# Power.net
KiCad netlist of a schematic drawn in Altium Designer
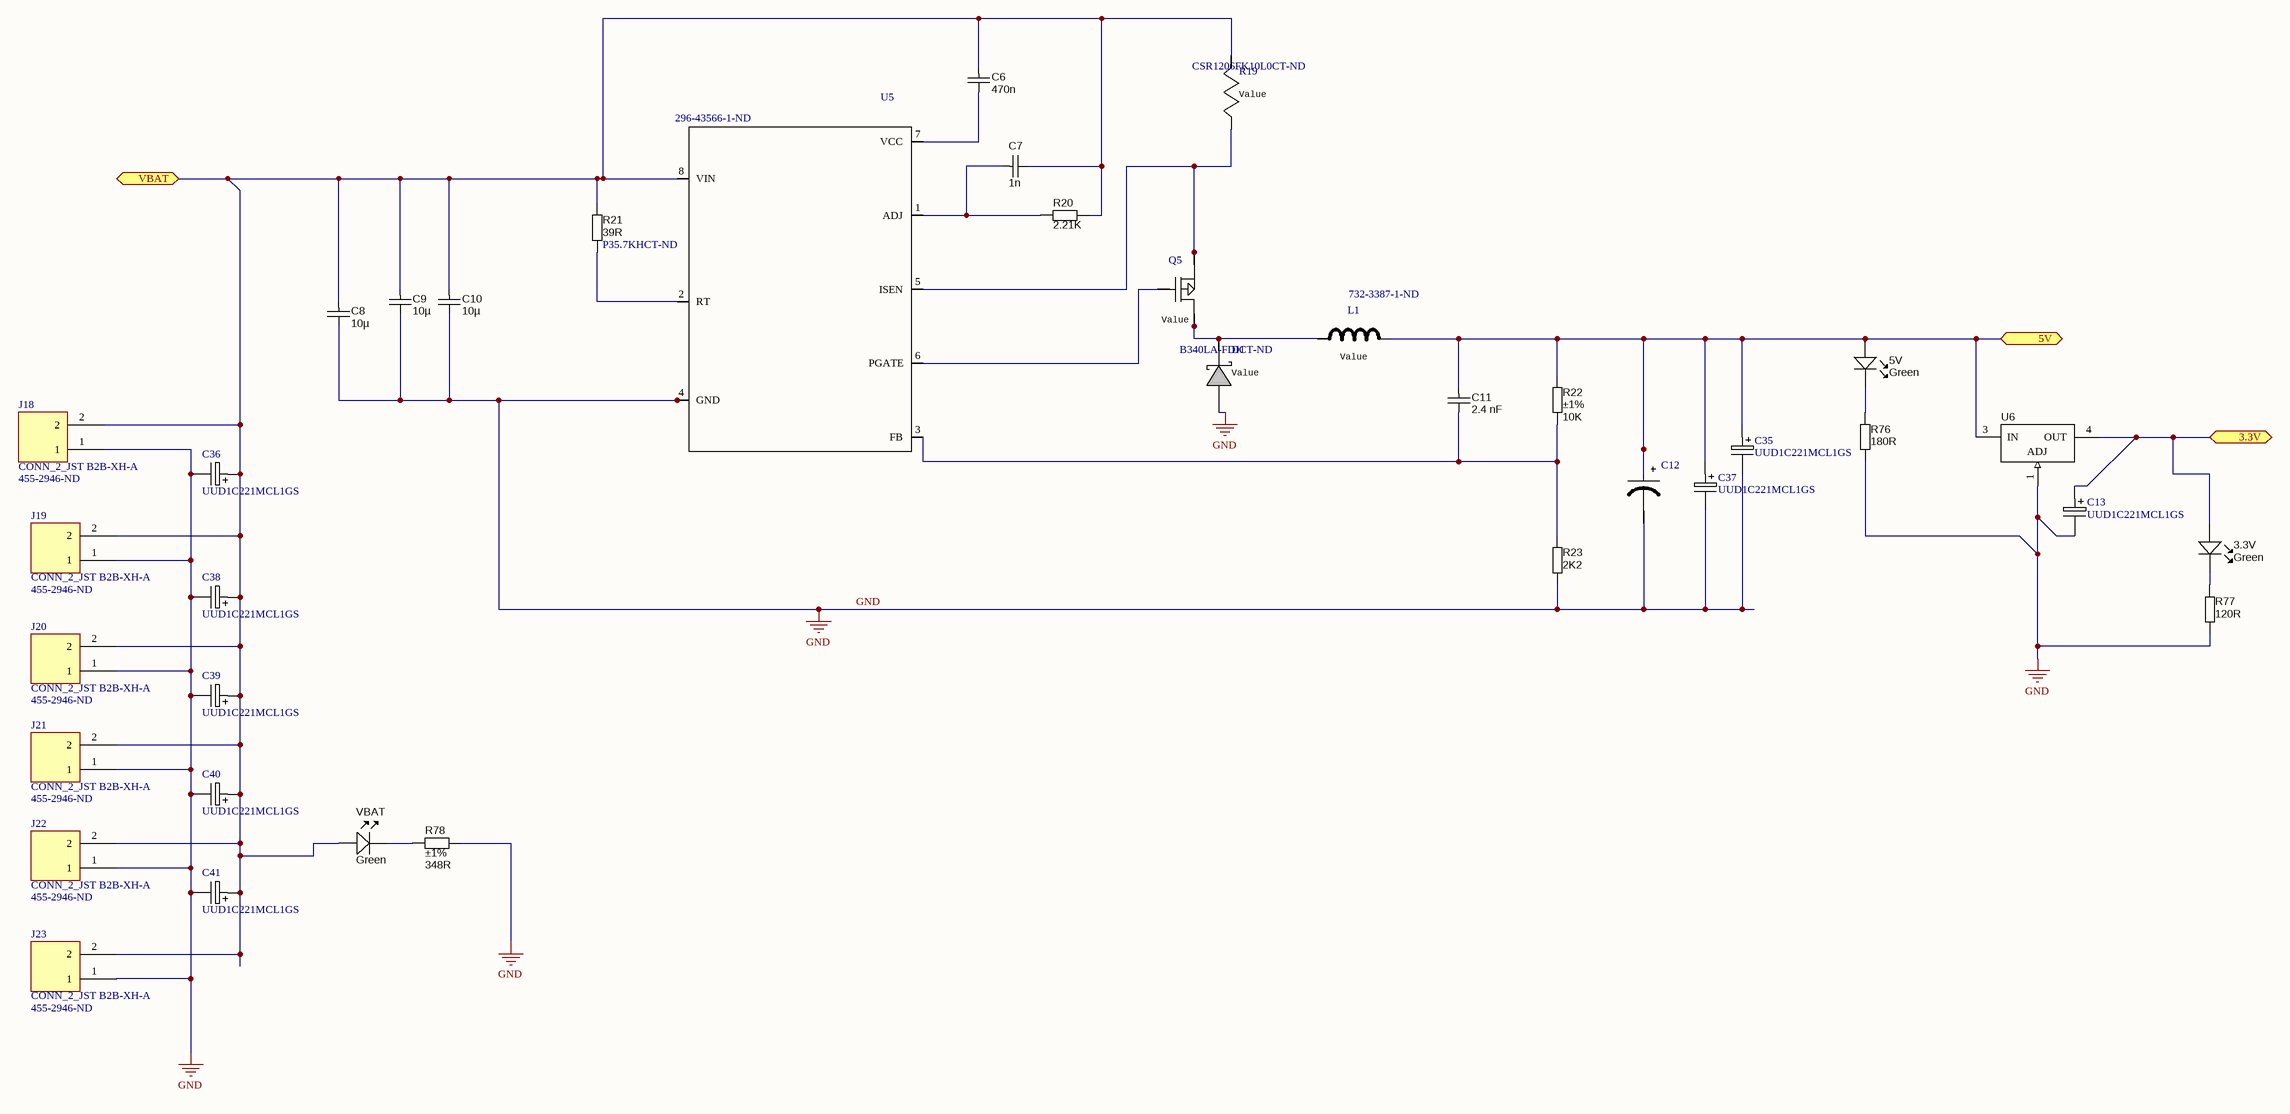
[diagram p0: Power.schdoc]

(export (version "E")
  (design (tool "Eeschema 10.0.6"))
  (components
    (comp (ref "3.3V")
      (value "Green")
      (footprint "LED-0603-GREEN")
      (description "LED 0603 SMD Green 525nm 350mcd 20mA")
      (libsource (lib "PBL - Light Sources") (part "LED_SMD_Green_0603_525nm_350mcd"))
    )
    (comp (ref "5V")
      (value "Green")
      (footprint "LED-0603-GREEN")
      (description "LED 0603 SMD Green 525nm 350mcd 20mA")
      (libsource (lib "PBL - Light Sources") (part "LED_SMD_Green_0603_525nm_350mcd"))
    )
    (comp (ref "C6")
      (value "470n")
      (footprint "CAPC2012X135N")
      (description "Capacitor SMD Cer 470nF 10% 16V X7R 0805")
      (fields (field (name "TOLERANCE") "±10%") (field (name "Comment") "approved sub OK"))
      (libsource (lib "PBL - Capacitors") (part "CAPC_470n_0805_X7R_16V_10%"))
    )
    (comp (ref "C7")
      (value "1n")
      (footprint "CAPC1608X90N")
      (description "Capacitor SMD Cer 1nF 10% 100V X7R 0603")
      (fields (field (name "TOLERANCE") "±10%") (field (name "Comment") "approved sub OK"))
      (libsource (lib "PBL - Capacitors") (part "CAPC_1n_0603_X7R_100V_10%"))
    )
    (comp (ref "C8")
      (value "10µ")
      (footprint "CAPC3216X180N")
      (description "Capacitor SMD Cer 10uF 10% 16V X7R 1206")
      (fields (field (name "TOLERANCE") "±10%") (field (name "Comment") "approved sub OK"))
      (libsource (lib "PBL - Capacitors") (part "CAPC_10u_1206_16V"))
    )
    (comp (ref "C9")
      (value "10µ")
      (footprint "CAPC3216X180N")
      (description "Capacitor SMD Cer 10uF 10% 16V X7R 1206")
      (fields (field (name "TOLERANCE") "±10%") (field (name "Comment") "approved sub OK"))
      (libsource (lib "PBL - Capacitors") (part "CAPC_10u_1206_16V"))
    )
    (comp (ref "C10")
      (value "10µ")
      (footprint "CAPC3216X180N")
      (description "Capacitor SMD Cer 10uF 10% 16V X7R 1206")
      (fields (field (name "TOLERANCE") "±10%") (field (name "Comment") "approved sub OK"))
      (libsource (lib "PBL - Capacitors") (part "CAPC_10u_1206_16V"))
    )
    (comp (ref "C11")
      (value "2.4 nF")
      (footprint "CAPC1608X90N")
      (description "Capacitor SMD Cer 2400pF  50V NP0 0603")
      (fields (field (name "TOLERANCE") "±0.25pF") (field (name "Comment") "approved sub OK"))
      (libsource (lib "PBL - Capacitors") (part "CAPC_2n4_50V_0603"))
    )
    (comp (ref "C12")
      (value "6TPU47MSI")
      (footprint "CAPC2012X135N")
      (description "CAP TANT POLY 47UF 6.3V 0805")
      (libsource (lib "PBL - Capacitors") (part "CAPT_47u_6.3V_0805_6TPU47MSI"))
    )
    (comp (ref "C13")
      (value "UUD1C221MCL1GS")
      (footprint "NICH 6.3mm 7.7mm")
      (description "GENERIC CAPACITOR POLARISED")
      (libsource (lib "SMD Capacitors Electrolytic") (part "NICHICON_220uF_16V"))
    )
    (comp (ref "C35")
      (value "UUD1C221MCL1GS")
      (footprint "NICH 6.3mm 7.7mm")
      (description "GENERIC CAPACITOR POLARISED")
      (libsource (lib "SMD Capacitors Electrolytic") (part "NICHICON_220uF_16V"))
    )
    (comp (ref "C36")
      (value "UUD1C221MCL1GS")
      (footprint "NICH 6.3mm 7.7mm")
      (description "GENERIC CAPACITOR POLARISED")
      (libsource (lib "SMD Capacitors Electrolytic") (part "NICHICON_220uF_16V"))
    )
    (comp (ref "C37")
      (value "UUD1C221MCL1GS")
      (footprint "NICH 6.3mm 7.7mm")
      (description "GENERIC CAPACITOR POLARISED")
      (libsource (lib "SMD Capacitors Electrolytic") (part "NICHICON_220uF_16V"))
    )
    (comp (ref "C38")
      (value "UUD1C221MCL1GS")
      (footprint "NICH 6.3mm 7.7mm")
      (description "GENERIC CAPACITOR POLARISED")
      (libsource (lib "SMD Capacitors Electrolytic") (part "NICHICON_220uF_16V"))
    )
    (comp (ref "C39")
      (value "UUD1C221MCL1GS")
      (footprint "NICH 6.3mm 7.7mm")
      (description "GENERIC CAPACITOR POLARISED")
      (libsource (lib "SMD Capacitors Electrolytic") (part "NICHICON_220uF_16V"))
    )
    (comp (ref "C40")
      (value "UUD1C221MCL1GS")
      (footprint "NICH 6.3mm 7.7mm")
      (description "GENERIC CAPACITOR POLARISED")
      (libsource (lib "SMD Capacitors Electrolytic") (part "NICHICON_220uF_16V"))
    )
    (comp (ref "C41")
      (value "UUD1C221MCL1GS")
      (footprint "NICH 6.3mm 7.7mm")
      (description "GENERIC CAPACITOR POLARISED")
      (libsource (lib "SMD Capacitors Electrolytic") (part "NICHICON_220uF_16V"))
    )
    (comp (ref "D1")
      (value "Value")
      (footprint "SMA")
      (description "Imported")
      (fields
        (field (name "MANUFACTURER_PART_NUMBER") "B340LA-13-F")
        (field (name "SUPPLIER PART NUMBER 1") "B340LA-FDICT-ND")
      )
      (libsource (lib "2016-02-21_13-02-55") (part "B340LA-13-F"))
    )
    (comp (ref "J18")
      (value "CONN_2_JST B2B-XH-A")
      (footprint "CONN_JST_XT_TH_2")
      (description "CONN HEADER XH SIDE 2POS 2.5MM")
      (fields (field (name "SUPPLIER PART NUMBER 1") "455-2946-ND"))
      (libsource (lib "RyanMasterLib") (part "CONN_2_JST B2B-XH-A"))
    )
    (comp (ref "J19")
      (value "CONN_2_JST B2B-XH-A")
      (footprint "CONN_JST_XT_TH_2")
      (description "CONN HEADER XH SIDE 2POS 2.5MM")
      (fields (field (name "SUPPLIER PART NUMBER 1") "455-2946-ND"))
      (libsource (lib "RyanMasterLib") (part "CONN_2_JST B2B-XH-A"))
    )
    (comp (ref "J20")
      (value "CONN_2_JST B2B-XH-A")
      (footprint "CONN_JST_XT_TH_2")
      (description "CONN HEADER XH SIDE 2POS 2.5MM")
      (fields (field (name "SUPPLIER PART NUMBER 1") "455-2946-ND"))
      (libsource (lib "RyanMasterLib") (part "CONN_2_JST B2B-XH-A"))
    )
    (comp (ref "J21")
      (value "CONN_2_JST B2B-XH-A")
      (footprint "CONN_JST_XT_TH_2")
      (description "CONN HEADER XH SIDE 2POS 2.5MM")
      (fields (field (name "SUPPLIER PART NUMBER 1") "455-2946-ND"))
      (libsource (lib "RyanMasterLib") (part "CONN_2_JST B2B-XH-A"))
    )
    (comp (ref "J22")
      (value "CONN_2_JST B2B-XH-A")
      (footprint "CONN_JST_XT_TH_2")
      (description "CONN HEADER XH SIDE 2POS 2.5MM")
      (fields (field (name "SUPPLIER PART NUMBER 1") "455-2946-ND"))
      (libsource (lib "RyanMasterLib") (part "CONN_2_JST B2B-XH-A"))
    )
    (comp (ref "J23")
      (value "CONN_2_JST B2B-XH-A")
      (footprint "CONN_JST_XT_TH_2")
      (description "CONN HEADER XH SIDE 2POS 2.5MM")
      (fields (field (name "SUPPLIER PART NUMBER 1") "455-2946-ND"))
      (libsource (lib "RyanMasterLib") (part "CONN_2_JST B2B-XH-A"))
    )
    (comp (ref "L1")
      (value "Value")
      (footprint "IND_WE-LHMI-SM")
      (description "Imported")
      (fields
        (field (name "MANUFACTURER_PART_NUMBER") "74437368022")
        (field (name "MANUFACTURER") "Wurth Elektronik")
        (field (name "SUPPLIER PART NUMBER 1") "732-3387-1-ND")
      )
      (libsource (lib "2016-02-21_13-02-55") (part "74437368022"))
    )
    (comp (ref "Q5")
      (value "Value")
      (footprint "TRANS_NEXFET_Q3A")
      (description "Imported")
      (fields (field (name "PARTNUMBER") "CSD25402Q3A") (field (name "MANUFACTURER") "Texas Instruments"))
      (libsource (lib "2016-02-21_13-02-55") (part "CSD25402Q3A"))
    )
    (comp (ref "R19")
      (value "Value")
      (footprint "1206")
      (description "Imported")
      (fields
        (field (name "MANUFACTURER_PART_NUMBER") "CSR1206FK10L0")
        (field (name "SUPPLIER PART NUMBER 1") "CSR1206FK10L0CT-ND")
      )
      (libsource (lib "2016-02-21_13-02-55") (part "CSR1206FK10L0"))
    )
    (comp (ref "R20")
      (value "2.21K")
      (footprint "RESC1608X55N")
      (description "Resistor SMD chip 2.21k Ohm 0.1W 1% 0603")
      (fields (field (name "TOLERANCE") "±5%") (field (name "Comment") "Thick Film"))
      (libsource (lib "PBL - Resistors") (part "RES_2.21K_0603_1%"))
    )
    (comp (ref "R21")
      (value "39R")
      (footprint "RESC1608X55N")
      (description "Resistor SMD chip 35.7K Ohm 0.1W 1% 0603")
      (fields
        (field (name "TOLERANCE") "±5%")
        (field (name "SUPPLIER PART NUMBER 1") "P35.7KHCT-ND")
        (field (name "Comment") "Thick Film")
      )
      (libsource (lib "PBL - Resistors") (part "RES_35.7K_0603_1%"))
    )
    (comp (ref "R22")
      (value "10K")
      (footprint "RESC1608X55N")
      (description "Resistor SMD chip 10k Ohm 0.1W 1% 0603")
      (fields (field (name "TOLERANCE") "±1%") (field (name "Comment") "Thick Film"))
      (libsource (lib "PBL - Resistors") (part "RES_10K_0603_1%"))
    )
    (comp (ref "R23")
      (value "2K2")
      (footprint "RESC1608X55N")
      (description "Resistor SMD chip 2.2k Ohm 0.1W 1% 0603")
      (fields (field (name "TOLERANCE") "±5%") (field (name "Comment") "Thick Film"))
      (libsource (lib "PBL - Resistors") (part "RES_2K2_0603_1%"))
    )
    (comp (ref "R76")
      (value "180R")
      (footprint "RESC1608X55N")
      (description "Resistor SMD chip 180 Ohm 0.1W 5% 0603")
      (fields (field (name "TOLERANCE") "±5%") (field (name "Comment") "Thick Film"))
      (libsource (lib "PBL - Resistors") (part "RES_180R_0603_5%"))
    )
    (comp (ref "R77")
      (value "120R")
      (footprint "RESC1608X55N")
      (description "Resistor SMD chip 120 Ohm 0.1W 5% 0603")
      (fields (field (name "TOLERANCE") "±5%") (field (name "Comment") "Thick Film"))
      (libsource (lib "PBL - Resistors") (part "RES_120R_0603_5%"))
    )
    (comp (ref "R78")
      (value "348R")
      (footprint "RESC1608X55N")
      (description "Resistor SMD chip 348 Ohm 0.1W 1% 0603")
      (fields (field (name "TOLERANCE") "±1%") (field (name "Comment") "Thin Film"))
      (libsource (lib "PBL - Resistors") (part "RES_348R_0603_1%"))
    )
    (comp (ref "U5")
      (value "LM25085AMY/NOPB")
      (footprint "MUY08A")
      (description "Imported")
      (fields
        (field (name "MANUFACTURER_PART_NUMBER") "LM5085MY/NOPB")
        (field (name "SUPPLIER PART NUMBER 1") "296-43566-1-ND")
      )
      (libsource (lib "2016-02-21_13-02-55") (part "LM25085AMY/NOPB"))
    )
    (comp (ref "U6")
      (value "LD1085D2T33R")
      (footprint "D2PAK-3")
      (description "Voltage Regulator IC, IC REG LDO 3.3V 3A D2PAK")
      (fields (field (name "TOLERANCE") "0.04%"))
      (libsource (lib "PBL - Regulators") (part "LD1085D2T33R"))
    )
    (comp (ref "VBAT")
      (value "Green")
      (footprint "LED-0603-GREEN")
      (description "LED 0603 SMD Green 525nm 350mcd 20mA")
      (libsource (lib "PBL - Light Sources") (part "LED_SMD_Green_0603_525nm_350mcd"))
    )
  )
  (nets
    (net (code "1") (name "/3.3V") (class "Default")
      (node (ref "3.3V") (pin "A") (pinfunction "A_A") (pintype "passive"))
      (node (ref "C13") (pin "+") (pinfunction "+_+") (pintype "passive"))
      (node (ref "U6") (pin "4") (pinfunction "OUT_4") (pintype "power_in"))
    )
    (net (code "2") (name "/5V") (class "Default")
      (node (ref "5V") (pin "A") (pinfunction "A_A") (pintype "passive"))
      (node (ref "C11") (pin "1") (pintype "passive"))
      (node (ref "C12") (pin "1") (pinfunction "+_1") (pintype "passive"))
      (node (ref "C35") (pin "+") (pinfunction "+_+") (pintype "passive"))
      (node (ref "C37") (pin "+") (pinfunction "+_+") (pintype "passive"))
      (node (ref "L1") (pin "2") (pinfunction "2_2") (pintype "passive"))
      (node (ref "R22") (pin "1") (pinfunction "1_1") (pintype "passive"))
      (node (ref "U6") (pin "3") (pinfunction "IN_3") (pintype "power_in"))
    )
    (net (code "3") (name "/VBAT") (class "Default")
      (node (ref "C10") (pin "1") (pintype "passive"))
      (node (ref "C36") (pin "+") (pinfunction "+_+") (pintype "passive"))
      (node (ref "C38") (pin "+") (pinfunction "+_+") (pintype "passive"))
      (node (ref "C39") (pin "+") (pinfunction "+_+") (pintype "passive"))
      (node (ref "C40") (pin "+") (pinfunction "+_+") (pintype "passive"))
      (node (ref "C41") (pin "+") (pinfunction "+_+") (pintype "passive"))
      (node (ref "C6") (pin "1") (pintype "passive"))
      (node (ref "C7") (pin "2") (pintype "passive"))
      (node (ref "C8") (pin "1") (pintype "passive"))
      (node (ref "C9") (pin "1") (pintype "passive"))
      (node (ref "J18") (pin "2") (pinfunction "2_2") (pintype "passive"))
      (node (ref "J19") (pin "2") (pinfunction "2_2") (pintype "passive"))
      (node (ref "J20") (pin "2") (pinfunction "2_2") (pintype "passive"))
      (node (ref "J21") (pin "2") (pinfunction "2_2") (pintype "passive"))
      (node (ref "J22") (pin "2") (pinfunction "2_2") (pintype "passive"))
      (node (ref "J23") (pin "2") (pinfunction "2_2") (pintype "passive"))
      (node (ref "R19") (pin "1") (pinfunction "1_1") (pintype "passive"))
      (node (ref "R20") (pin "2") (pinfunction "2_2") (pintype "passive"))
      (node (ref "R21") (pin "1") (pinfunction "1_1") (pintype "passive"))
      (node (ref "U5") (pin "8") (pinfunction "VIN_8") (pintype "passive"))
      (node (ref "VBAT") (pin "A") (pinfunction "A_A") (pintype "passive"))
    )
    (net (code "4") (name "GND") (class "Default")
      (node (ref "C10") (pin "2") (pintype "passive"))
      (node (ref "C12") (pin "2") (pinfunction "-_2") (pintype "passive"))
      (node (ref "C13") (pin "-") (pinfunction "-_-") (pintype "passive"))
      (node (ref "C35") (pin "-") (pinfunction "-_-") (pintype "passive"))
      (node (ref "C36") (pin "-") (pinfunction "-_-") (pintype "passive"))
      (node (ref "C37") (pin "-") (pinfunction "-_-") (pintype "passive"))
      (node (ref "C38") (pin "-") (pinfunction "-_-") (pintype "passive"))
      (node (ref "C39") (pin "-") (pinfunction "-_-") (pintype "passive"))
      (node (ref "C40") (pin "-") (pinfunction "-_-") (pintype "passive"))
      (node (ref "C41") (pin "-") (pinfunction "-_-") (pintype "passive"))
      (node (ref "C8") (pin "2") (pintype "passive"))
      (node (ref "C9") (pin "2") (pintype "passive"))
      (node (ref "D1") (pin "2") (pinfunction "A_2") (pintype "passive"))
      (node (ref "J18") (pin "1") (pinfunction "1_1") (pintype "passive"))
      (node (ref "J19") (pin "1") (pinfunction "1_1") (pintype "passive"))
      (node (ref "J20") (pin "1") (pinfunction "1_1") (pintype "passive"))
      (node (ref "J21") (pin "1") (pinfunction "1_1") (pintype "passive"))
      (node (ref "J22") (pin "1") (pinfunction "1_1") (pintype "passive"))
      (node (ref "J23") (pin "1") (pinfunction "1_1") (pintype "passive"))
      (node (ref "R23") (pin "2") (pinfunction "2_2") (pintype "passive"))
      (node (ref "R76") (pin "2") (pinfunction "2_2") (pintype "passive"))
      (node (ref "R77") (pin "2") (pinfunction "2_2") (pintype "passive"))
      (node (ref "R78") (pin "2") (pinfunction "2_2") (pintype "passive"))
      (node (ref "U5") (pin "4") (pinfunction "GND_4") (pintype "passive"))
      (node (ref "U5") (pin "9") (pinfunction "GND_9") (pintype "passive"))
      (node (ref "U6") (pin "1") (pinfunction "ADJ_1") (pintype "input"))
    )
    (net (code "5") (name "Net-(3.3V-PadK)") (class "Default")
      (node (ref "3.3V") (pin "K") (pinfunction "K_K") (pintype "passive"))
      (node (ref "R77") (pin "1") (pinfunction "1_1") (pintype "passive"))
    )
    (net (code "6") (name "Net-(5V-PadK)") (class "Default")
      (node (ref "5V") (pin "K") (pinfunction "K_K") (pintype "passive"))
      (node (ref "R76") (pin "1") (pinfunction "1_1") (pintype "passive"))
    )
    (net (code "7") (name "Net-(D1-K)") (class "Default")
      (node (ref "D1") (pin "1") (pinfunction "K_1") (pintype "passive"))
      (node (ref "L1") (pin "1") (pinfunction "1_1") (pintype "passive"))
      (node (ref "Q5") (pin "1") (pinfunction "Drain_1") (pintype "passive"))
      (node (ref "Q5") (pin "2") (pinfunction "Drain_2") (pintype "passive"))
      (node (ref "Q5") (pin "3") (pinfunction "Drain_3") (pintype "passive"))
    )
    (net (code "8") (name "Net-(Q5-Gate)") (class "Default")
      (node (ref "Q5") (pin "4") (pinfunction "Gate_4") (pintype "passive"))
      (node (ref "U5") (pin "6") (pinfunction "PGATE_6") (pintype "passive"))
    )
    (net (code "9") (name "Net-(R78-Pad1)") (class "Default")
      (node (ref "R78") (pin "1") (pinfunction "1_1") (pintype "passive"))
      (node (ref "VBAT") (pin "K") (pinfunction "K_K") (pintype "passive"))
    )
    (net (code "10") (name "Net-(U5-ADJ)") (class "Default")
      (node (ref "C7") (pin "1") (pintype "passive"))
      (node (ref "R20") (pin "1") (pinfunction "1_1") (pintype "passive"))
      (node (ref "U5") (pin "1") (pinfunction "ADJ_1") (pintype "passive"))
    )
    (net (code "11") (name "Net-(U5-FB)") (class "Default")
      (node (ref "C11") (pin "2") (pintype "passive"))
      (node (ref "R22") (pin "2") (pinfunction "2_2") (pintype "passive"))
      (node (ref "R23") (pin "1") (pinfunction "1_1") (pintype "passive"))
      (node (ref "U5") (pin "3") (pinfunction "FB_3") (pintype "passive"))
    )
    (net (code "12") (name "Net-(U5-ISEN)") (class "Default")
      (node (ref "Q5") (pin "5") (pinfunction "Source_5") (pintype "passive"))
      (node (ref "Q5") (pin "6") (pinfunction "Source_6") (pintype "passive"))
      (node (ref "Q5") (pin "7") (pinfunction "Source_7") (pintype "passive"))
      (node (ref "Q5") (pin "8") (pinfunction "Source_8") (pintype "passive"))
      (node (ref "Q5") (pin "9") (pinfunction "Source_9") (pintype "passive"))
      (node (ref "R19") (pin "2") (pinfunction "2_2") (pintype "passive"))
      (node (ref "U5") (pin "5") (pinfunction "ISEN_5") (pintype "passive"))
    )
    (net (code "13") (name "Net-(U5-RT)") (class "Default")
      (node (ref "R21") (pin "2") (pinfunction "2_2") (pintype "passive"))
      (node (ref "U5") (pin "2") (pinfunction "RT_2") (pintype "passive"))
    )
    (net (code "14") (name "Net-(U5-VCC)") (class "Default")
      (node (ref "C6") (pin "2") (pintype "passive"))
      (node (ref "U5") (pin "7") (pinfunction "VCC_7") (pintype "passive"))
    )
  )
)
